# 6_-_Position2Go_Debugger.net
KiCad netlist of a schematic drawn in Altium Designer
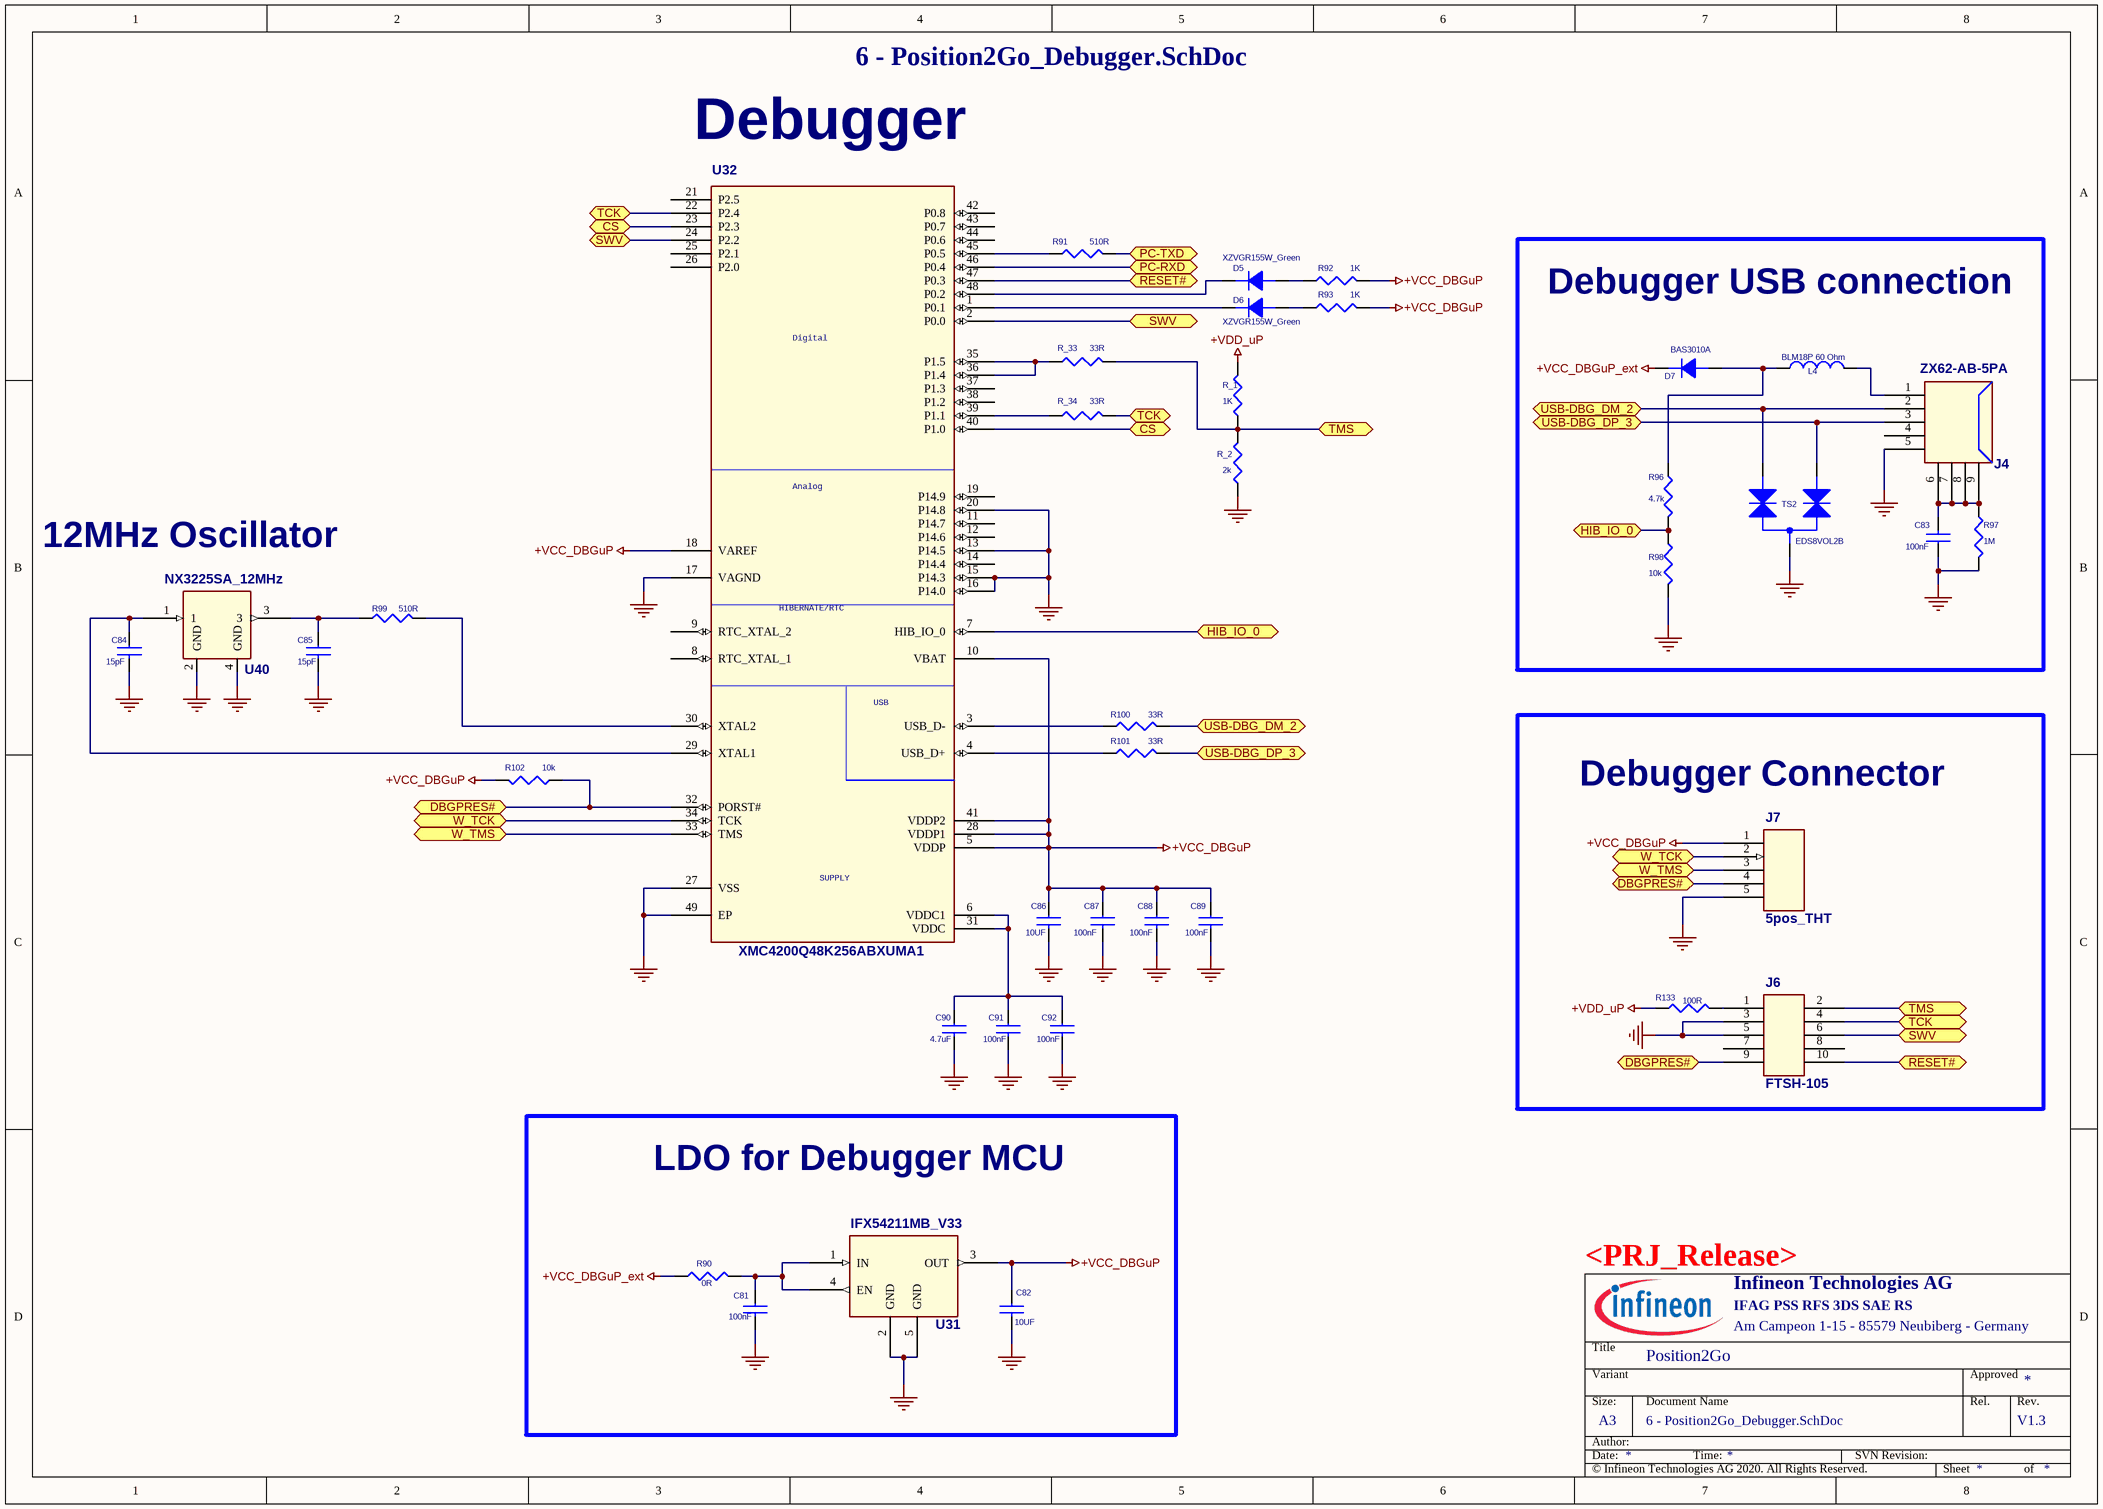
[diagram p0: 6 - Position2Go_Debugger.SchDoc]

(export (version "E")
  (design (tool "Eeschema 10.0.6"))
  (components
    (comp (ref "C81")
      (value "100nF")
      (footprint "0402_durac")
      (description "100nF  ±5%  16V  X7R")
      (fields (field (name "TOLERANCE") "5%") (field (name "VOLTAGE") "16V"))
      (libsource (lib "*") (part "100nF"))
    )
    (comp (ref "C82")
      (value "10UF")
      (footprint "0402_durac")
      (fields (field (name "TOLERANCE") "20%") (field (name "VOLTAGE") "10V"))
      (libsource (lib "*") (part "10UF"))
    )
    (comp (ref "C83")
      (value "100nF")
      (footprint "0402_durac")
      (description "100nF  ±5%  16V  X7R")
      (libsource (lib "*") (part "CAP NP"))
    )
    (comp (ref "C84")
      (value "15pF")
      (footprint "0402_durac")
      (fields (field (name "TOLERANCE") "+-0.1pF") (field (name "VOLTAGE") "50V"))
      (libsource (lib "*") (part "15pF"))
    )
    (comp (ref "C85")
      (value "15pF")
      (footprint "0402_durac")
      (fields (field (name "TOLERANCE") "+-0.1pF") (field (name "VOLTAGE") "50V"))
      (libsource (lib "*") (part "15pF"))
    )
    (comp (ref "C86")
      (value "10UF")
      (footprint "0402_durac")
      (fields (field (name "TOLERANCE") "20%") (field (name "VOLTAGE") "10V"))
      (libsource (lib "*") (part "10UF"))
    )
    (comp (ref "C87")
      (value "100nF")
      (footprint "0402_durac")
      (description "100nF  ±5%  16V  X7R")
      (fields (field (name "TOLERANCE") "5%") (field (name "VOLTAGE") "16V"))
      (libsource (lib "*") (part "100nF"))
    )
    (comp (ref "C88")
      (value "100nF")
      (footprint "0402_durac")
      (description "100nF  ±5%  16V  X7R")
      (fields (field (name "TOLERANCE") "5%") (field (name "VOLTAGE") "16V"))
      (libsource (lib "*") (part "100nF"))
    )
    (comp (ref "C89")
      (value "100nF")
      (footprint "0402_durac")
      (description "100nF  ±5%  16V  X7R")
      (fields (field (name "TOLERANCE") "5%") (field (name "VOLTAGE") "16V"))
      (libsource (lib "*") (part "100nF"))
    )
    (comp (ref "C90")
      (value "4.7uF")
      (footprint "0402_durac")
      (fields (field (name "VOLTAGE") "10V") (field (name "TOLERANCE") "10%"))
      (libsource (lib "*") (part "4.7UF"))
    )
    (comp (ref "C91")
      (value "100nF")
      (footprint "0402_durac")
      (description "100nF  ±5%  16V  X7R")
      (fields (field (name "TOLERANCE") "5%") (field (name "VOLTAGE") "16V"))
      (libsource (lib "*") (part "100nF"))
    )
    (comp (ref "C92")
      (value "100nF")
      (footprint "0402_durac")
      (description "100nF  ±5%  16V  X7R")
      (fields (field (name "TOLERANCE") "5%") (field (name "VOLTAGE") "16V"))
      (libsource (lib "*") (part "100nF"))
    )
    (comp (ref "D5")
      (value "XZVGR155W_Green")
      (footprint "LED_0201")
      (libsource (lib "*") (part "LED_0201_GREEN"))
    )
    (comp (ref "D6")
      (value "XZVGR155W_Green")
      (footprint "LED_0201")
      (libsource (lib "*") (part "LED_0201_GREEN"))
    )
    (comp (ref "D7") (value "BAS3010A") (footprint "sod323") (libsource (lib "*") (part "BAS3010A")))
    (comp (ref "J4")
      (value "ZX62-AB-5PA")
      (footprint "micro_AB_ZX62")
      (libsource (lib "*") (part "CON_MICRO_AB"))
    )
    (comp (ref "J6")
      (value "FTSH-105")
      (footprint "CON_10_pin_uP_FTSH")
      (libsource (lib "*") (part "CON_10_pin_uP_FTSH"))
    )
    (comp (ref "J7")
      (value "5pos_THT")
      (footprint "con_5pin_254p")
      (libsource (lib "*") (part "5pos_TH_passo2_54"))
    )
    (comp (ref "L4")
      (value "BLM18P 60 Ohm")
      (footprint "L_0603")
      (libsource (lib "*") (part "blm18 p 60 ohm"))
    )
    (comp (ref "R90")
      (value "0R")
      (footprint "0402_durac")
      (description "04 0402")
      (fields (field (name "POWER") "0.063W") (field (name "TOLERANCE") "1%"))
      (libsource (lib "*") (part "0_Dup1"))
    )
    (comp (ref "R91")
      (value "510R")
      (footprint "0402_durac")
      (fields (field (name "POWER") "0.063W") (field (name "TOLERANCE") "1%"))
      (libsource (lib "*") (part "510"))
    )
    (comp (ref "R92")
      (value "1K")
      (footprint "R_0201")
      (fields (field (name "POWER") "0.063W") (field (name "TOLERANCE") "1%"))
      (libsource (lib "*") (part "1K"))
    )
    (comp (ref "R93")
      (value "1K")
      (footprint "R_0201")
      (fields (field (name "POWER") "0.063W") (field (name "TOLERANCE") "1%"))
      (libsource (lib "*") (part "1K"))
    )
    (comp (ref "R96")
      (value "4.7k")
      (footprint "0402_durac")
      (fields (field (name "TOLERANCE") "1%") (field (name "POWER") "0.063W"))
      (libsource (lib "*") (part "4.7K"))
    )
    (comp (ref "R97") (value "1M") (footprint "0402_durac") (libsource (lib "*") (part "RESISTOR")))
    (comp (ref "R98")
      (value "10k")
      (footprint "0402_durac")
      (fields (field (name "TOLERANCE") "1%") (field (name "POWER") "0.063W"))
      (libsource (lib "*") (part "10K"))
    )
    (comp (ref "R99")
      (value "510R")
      (footprint "0402_durac")
      (fields (field (name "POWER") "0.063W") (field (name "TOLERANCE") "1%"))
      (libsource (lib "*") (part "510"))
    )
    (comp (ref "R100")
      (value "33R")
      (footprint "0402_durac")
      (fields (field (name "POWER") "0.063W") (field (name "TOLERANCE") "1%"))
      (libsource (lib "*") (part "33"))
    )
    (comp (ref "R101")
      (value "33R")
      (footprint "0402_durac")
      (fields (field (name "POWER") "0.063W") (field (name "TOLERANCE") "1%"))
      (libsource (lib "*") (part "33"))
    )
    (comp (ref "R102")
      (value "10k")
      (footprint "0402_durac")
      (fields (field (name "TOLERANCE") "1%") (field (name "POWER") "0.063W"))
      (libsource (lib "*") (part "10K"))
    )
    (comp (ref "R133") (value "100R") (footprint "0402_durac") (libsource (lib "*") (part "RESISTOR")))
    (comp (ref "R_1")
      (value "1K")
      (footprint "R_0201")
      (fields (field (name "POWER") "0.063W") (field (name "TOLERANCE") "1%"))
      (libsource (lib "*") (part "1K"))
    )
    (comp (ref "R_2")
      (value "2k")
      (footprint "R_0201")
      (fields (field (name "POWER") "0.063W") (field (name "TOLERANCE") "1%"))
      (libsource (lib "*") (part "1K"))
    )
    (comp (ref "R_33")
      (value "33R")
      (footprint "R_0201")
      (fields (field (name "POWER") "0.063W") (field (name "TOLERANCE") "1%"))
      (libsource (lib "*") (part "1K"))
    )
    (comp (ref "R_34")
      (value "33R")
      (footprint "R_0201")
      (fields (field (name "POWER") "0.063W") (field (name "TOLERANCE") "1%"))
      (libsource (lib "*") (part "1K"))
    )
    (comp (ref "TS2") (value "EDS8VOL2B") (footprint "ESD8VOL2B") (libsource (lib "*") (part "ESD8VOL2B")))
    (comp (ref "U31")
      (value "IFX54211MB_V33")
      (footprint "inf-pg-sct595v")
      (libsource (lib "*") (part "IFX54211MB_V33"))
    )
    (comp (ref "U32")
      (value "XMC4200Q48K256ABXUMA1")
      (footprint "inf-pg-vqfn-48-_-5200x5200tp_n")
      (libsource (lib "*") (part "XMC4200_VQFN48"))
    )
    (comp (ref "U40")
      (value "NX3225SA_12MHz")
      (footprint "NX3225SA")
      (description "NX3225SA-12.000M-STD-CRS-2")
      (libsource (lib "*") (part "NX3225SA_12MHZ"))
    )
  )
  (nets
    (net (code "1") (name "+VCC_DBGuP") (class "Default")
      (node (ref "C82") (pin "1") (pinfunction "1_1") (pintype "passive"))
      (node (ref "C86") (pin "1") (pinfunction "1_1") (pintype "passive"))
      (node (ref "C87") (pin "1") (pinfunction "1_1") (pintype "passive"))
      (node (ref "C88") (pin "1") (pinfunction "1_1") (pintype "passive"))
      (node (ref "C89") (pin "1") (pinfunction "1_1") (pintype "passive"))
      (node (ref "J7") (pin "1") (pinfunction "1_1") (pintype "passive"))
      (node (ref "R102") (pin "2") (pinfunction "2_2") (pintype "passive"))
      (node (ref "R92") (pin "2") (pinfunction "2_2") (pintype "passive"))
      (node (ref "R93") (pin "2") (pinfunction "2_2") (pintype "passive"))
      (node (ref "U31") (pin "3") (pinfunction "OUT_3") (pintype "output"))
      (node (ref "U32") (pin "10") (pinfunction "VBAT_10") (pintype "power_in"))
      (node (ref "U32") (pin "18") (pinfunction "VAREF_18") (pintype "power_in"))
      (node (ref "U32") (pin "28") (pinfunction "VDDP1_28") (pintype "power_in"))
      (node (ref "U32") (pin "41") (pinfunction "VDDP2_41") (pintype "power_in"))
      (node (ref "U32") (pin "5") (pinfunction "VDDP_5") (pintype "power_in"))
    )
    (net (code "2") (name "+VCC_DBGuP_ext") (class "Default")
      (node (ref "D7") (pin "1") (pinfunction "K_1") (pintype "passive"))
      (node (ref "R90") (pin "1") (pinfunction "1_1") (pintype "passive"))
    )
    (net (code "3") (name "+VDD_uP") (class "Default")
      (node (ref "R133") (pin "2") (pinfunction "2_2") (pintype "passive"))
      (node (ref "R_1") (pin "2") (pinfunction "2_2") (pintype "passive"))
    )
    (net (code "4") (name "/CS") (class "Default")
      (node (ref "U32") (pin "23") (pinfunction "P2.3_23") (pintype "passive"))
      (node (ref "U32") (pin "40") (pinfunction "P1.0_40") (pintype "bidirectional"))
    )
    (net (code "5") (name "/DBGPRES#") (class "Default")
      (node (ref "J6") (pin "9") (pinfunction "9_9") (pintype "passive"))
      (node (ref "J7") (pin "4") (pinfunction "4_4") (pintype "passive"))
      (node (ref "R102") (pin "1") (pinfunction "1_1") (pintype "passive"))
      (node (ref "U32") (pin "32") (pinfunction "PORST#_32") (pintype "bidirectional"))
    )
    (net (code "6") (name "/HIB_IO_0") (class "Default")
      (node (ref "R96") (pin "2") (pinfunction "2_2") (pintype "passive"))
      (node (ref "R98") (pin "1") (pinfunction "1_1") (pintype "passive"))
      (node (ref "U32") (pin "7") (pinfunction "HIB_IO_0_7") (pintype "bidirectional"))
    )
    (net (code "7") (name "/PC-RXD") (class "Default")
      (node (ref "U32") (pin "46") (pinfunction "P0.4_46") (pintype "bidirectional"))
    )
    (net (code "8") (name "/PC-TXD") (class "Default")
      (node (ref "R91") (pin "2") (pinfunction "2_2") (pintype "passive"))
    )
    (net (code "9") (name "/RESET#") (class "Default")
      (node (ref "J6") (pin "10") (pinfunction "10_10") (pintype "passive"))
      (node (ref "U32") (pin "47") (pinfunction "P0.3_47") (pintype "bidirectional"))
    )
    (net (code "10") (name "/SWV") (class "Default")
      (node (ref "J6") (pin "6") (pinfunction "6_6") (pintype "passive"))
      (node (ref "U32") (pin "2") (pinfunction "P0.0_2") (pintype "bidirectional"))
      (node (ref "U32") (pin "24") (pinfunction "P2.2_24") (pintype "passive"))
    )
    (net (code "11") (name "/TCK") (class "Default")
      (node (ref "J6") (pin "4") (pinfunction "4_4") (pintype "passive"))
      (node (ref "R_34") (pin "2") (pinfunction "2_2") (pintype "passive"))
      (node (ref "U32") (pin "22") (pinfunction "P2.4_22") (pintype "passive"))
    )
    (net (code "12") (name "/TMS") (class "Default")
      (node (ref "J6") (pin "2") (pinfunction "2_2") (pintype "passive"))
      (node (ref "R_1") (pin "1") (pinfunction "1_1") (pintype "passive"))
      (node (ref "R_2") (pin "2") (pinfunction "2_2") (pintype "passive"))
      (node (ref "R_33") (pin "2") (pinfunction "2_2") (pintype "passive"))
    )
    (net (code "13") (name "/USB-DBG_DM_2") (class "Default")
      (node (ref "J4") (pin "2") (pinfunction "2_2") (pintype "passive"))
      (node (ref "R100") (pin "2") (pinfunction "2_2") (pintype "passive"))
      (node (ref "TS2") (pin "1") (pinfunction "1_1") (pintype "passive"))
    )
    (net (code "14") (name "/USB-DBG_DP_3") (class "Default")
      (node (ref "J4") (pin "3") (pinfunction "3_3") (pintype "passive"))
      (node (ref "R101") (pin "2") (pinfunction "2_2") (pintype "passive"))
      (node (ref "TS2") (pin "2") (pinfunction "2_2") (pintype "passive"))
    )
    (net (code "15") (name "/W_TCK") (class "Default")
      (node (ref "J7") (pin "2") (pinfunction "2_2") (pintype "input"))
      (node (ref "U32") (pin "34") (pinfunction "TCK_34") (pintype "bidirectional"))
    )
    (net (code "16") (name "/W_TMS") (class "Default")
      (node (ref "J7") (pin "3") (pinfunction "3_3") (pintype "passive"))
      (node (ref "U32") (pin "33") (pinfunction "TMS_33") (pintype "bidirectional"))
    )
    (net (code "17") (name "GND_POWER") (class "Default")
      (node (ref "C81") (pin "2") (pinfunction "2_2") (pintype "passive"))
      (node (ref "C82") (pin "2") (pinfunction "2_2") (pintype "passive"))
      (node (ref "C83") (pin "1") (pinfunction "1_1") (pintype "passive"))
      (node (ref "C84") (pin "2") (pinfunction "2_2") (pintype "passive"))
      (node (ref "C85") (pin "2") (pinfunction "2_2") (pintype "passive"))
      (node (ref "C86") (pin "2") (pinfunction "2_2") (pintype "passive"))
      (node (ref "C87") (pin "2") (pinfunction "2_2") (pintype "passive"))
      (node (ref "C88") (pin "2") (pinfunction "2_2") (pintype "passive"))
      (node (ref "C89") (pin "2") (pinfunction "2_2") (pintype "passive"))
      (node (ref "C90") (pin "2") (pinfunction "2_2") (pintype "passive"))
      (node (ref "C91") (pin "2") (pinfunction "2_2") (pintype "passive"))
      (node (ref "C92") (pin "2") (pinfunction "2_2") (pintype "passive"))
      (node (ref "J4") (pin "5") (pinfunction "5_5") (pintype "passive"))
      (node (ref "J6") (pin "3") (pinfunction "3_3") (pintype "passive"))
      (node (ref "J6") (pin "5") (pinfunction "5_5") (pintype "passive"))
      (node (ref "J7") (pin "5") (pinfunction "5_5") (pintype "passive"))
      (node (ref "R97") (pin "2") (pinfunction "2_2") (pintype "passive"))
      (node (ref "R98") (pin "2") (pinfunction "2_2") (pintype "passive"))
      (node (ref "R_2") (pin "1") (pinfunction "1_1") (pintype "passive"))
      (node (ref "TS2") (pin "3") (pinfunction "3_3") (pintype "passive"))
      (node (ref "U31") (pin "2") (pinfunction "GND_2") (pintype "power_in"))
      (node (ref "U31") (pin "5") (pinfunction "GND_5") (pintype "power_in"))
      (node (ref "U32") (pin "13") (pinfunction "P14.5_13") (pintype "bidirectional"))
      (node (ref "U32") (pin "15") (pinfunction "P14.3_15") (pintype "bidirectional"))
      (node (ref "U32") (pin "16") (pinfunction "P14.0_16") (pintype "bidirectional"))
      (node (ref "U32") (pin "17") (pinfunction "VAGND_17") (pintype "power_in"))
      (node (ref "U32") (pin "20") (pinfunction "P14.8_20") (pintype "bidirectional"))
      (node (ref "U32") (pin "27") (pinfunction "VSS_27") (pintype "power_in"))
      (node (ref "U32") (pin "49") (pinfunction "EP_49") (pintype "power_in"))
      (node (ref "U40") (pin "2") (pinfunction "GND_2") (pintype "power_in"))
      (node (ref "U40") (pin "4") (pinfunction "GND_4") (pintype "power_in"))
    )
    (net (code "18") (name "Net-(C85-Pad1)") (class "Default")
      (node (ref "C85") (pin "1") (pinfunction "1_1") (pintype "passive"))
      (node (ref "R99") (pin "1") (pinfunction "1_1") (pintype "passive"))
      (node (ref "U40") (pin "3") (pinfunction "3_3") (pintype "output"))
    )
    (net (code "19") (name "Net-(D5-A)") (class "Default")
      (node (ref "D5") (pin "2") (pinfunction "A_2") (pintype "passive"))
      (node (ref "R92") (pin "1") (pinfunction "1_1") (pintype "passive"))
    )
    (net (code "20") (name "Net-(D5-K)") (class "Default")
      (node (ref "D5") (pin "1") (pinfunction "K_1") (pintype "passive"))
      (node (ref "U32") (pin "48") (pinfunction "P0.2_48") (pintype "bidirectional"))
    )
    (net (code "21") (name "Net-(D6-A)") (class "Default")
      (node (ref "D6") (pin "2") (pinfunction "A_2") (pintype "passive"))
      (node (ref "R93") (pin "1") (pinfunction "1_1") (pintype "passive"))
    )
    (net (code "22") (name "Net-(D6-K)") (class "Default")
      (node (ref "D6") (pin "1") (pinfunction "K_1") (pintype "passive"))
      (node (ref "U32") (pin "1") (pinfunction "P0.1_1") (pintype "bidirectional"))
    )
    (net (code "23") (name "Net-(D7-A)") (class "Default")
      (node (ref "D7") (pin "2") (pinfunction "A_2") (pintype "passive"))
      (node (ref "L4") (pin "2") (pinfunction "2_2") (pintype "passive"))
      (node (ref "R96") (pin "1") (pinfunction "1_1") (pintype "passive"))
    )
    (net (code "24") (name "Net-(J4-GNd)") (class "Default")
      (node (ref "C83") (pin "2") (pinfunction "2_2") (pintype "passive"))
      (node (ref "J4") (pin "6") (pinfunction "GND_6") (pintype "power_in"))
      (node (ref "J4") (pin "7") (pinfunction "GND_7") (pintype "power_in"))
      (node (ref "J4") (pin "8") (pinfunction "GND_8") (pintype "power_in"))
      (node (ref "J4") (pin "9") (pinfunction "GNd_9") (pintype "power_in"))
      (node (ref "R97") (pin "1") (pinfunction "1_1") (pintype "passive"))
    )
    (net (code "25") (name "Net-(J4-Pad1)") (class "Default")
      (node (ref "J4") (pin "1") (pinfunction "1_1") (pintype "passive"))
      (node (ref "L4") (pin "1") (pinfunction "1_1") (pintype "passive"))
    )
    (net (code "26") (name "Net-(J6-Pad1)") (class "Default")
      (node (ref "J6") (pin "1") (pinfunction "1_1") (pintype "passive"))
      (node (ref "R133") (pin "1") (pinfunction "1_1") (pintype "passive"))
    )
    (net (code "27") (name "Net-(U31-EN)") (class "Default")
      (node (ref "C81") (pin "1") (pinfunction "1_1") (pintype "passive"))
      (node (ref "R90") (pin "2") (pinfunction "2_2") (pintype "passive"))
      (node (ref "U31") (pin "1") (pinfunction "IN_1") (pintype "input"))
      (node (ref "U31") (pin "4") (pinfunction "EN_4") (pintype "output"))
    )
    (net (code "28") (name "Net-(U32-P0.5)") (class "Default")
      (node (ref "R91") (pin "1") (pinfunction "1_1") (pintype "passive"))
      (node (ref "U32") (pin "45") (pinfunction "P0.5_45") (pintype "bidirectional"))
    )
    (net (code "29") (name "Net-(U32-P1.1)") (class "Default")
      (node (ref "R_34") (pin "1") (pinfunction "1_1") (pintype "passive"))
      (node (ref "U32") (pin "39") (pinfunction "P1.1_39") (pintype "bidirectional"))
    )
    (net (code "30") (name "Net-(U32-P1.4)") (class "Default")
      (node (ref "R_33") (pin "1") (pinfunction "1_1") (pintype "passive"))
      (node (ref "U32") (pin "35") (pinfunction "P1.5_35") (pintype "bidirectional"))
      (node (ref "U32") (pin "36") (pinfunction "P1.4_36") (pintype "bidirectional"))
    )
    (net (code "31") (name "Net-(U32-USB_D+)") (class "Default")
      (node (ref "R101") (pin "1") (pinfunction "1_1") (pintype "passive"))
      (node (ref "U32") (pin "4") (pinfunction "USB_D+_4") (pintype "bidirectional"))
    )
    (net (code "32") (name "Net-(U32-USB_D-)") (class "Default")
      (node (ref "R100") (pin "1") (pinfunction "1_1") (pintype "passive"))
      (node (ref "U32") (pin "3") (pinfunction "USB_D-_3") (pintype "bidirectional"))
    )
    (net (code "33") (name "Net-(U32-VDDC)") (class "Default")
      (node (ref "C90") (pin "1") (pinfunction "1_1") (pintype "passive"))
      (node (ref "C91") (pin "1") (pinfunction "1_1") (pintype "passive"))
      (node (ref "C92") (pin "1") (pinfunction "1_1") (pintype "passive"))
      (node (ref "U32") (pin "31") (pinfunction "VDDC_31") (pintype "power_in"))
      (node (ref "U32") (pin "6") (pinfunction "VDDC1_6") (pintype "power_in"))
    )
    (net (code "34") (name "Net-(U32-XTAL1)") (class "Default")
      (node (ref "C84") (pin "1") (pinfunction "1_1") (pintype "passive"))
      (node (ref "U32") (pin "29") (pinfunction "XTAL1_29") (pintype "bidirectional"))
      (node (ref "U40") (pin "1") (pinfunction "1_1") (pintype "input"))
    )
    (net (code "35") (name "Net-(U32-XTAL2)") (class "Default")
      (node (ref "R99") (pin "2") (pinfunction "2_2") (pintype "passive"))
      (node (ref "U32") (pin "30") (pinfunction "XTAL2_30") (pintype "bidirectional"))
    )
    (net (code "36") (name "unconnected-(J4-Pad4)") (class "Default")
      (node (ref "J4") (pin "4") (pinfunction "4_4") (pintype "passive"))
    )
    (net (code "37") (name "unconnected-(J6-Pad7)") (class "Default")
      (node (ref "J6") (pin "7") (pinfunction "7_7") (pintype "passive"))
    )
    (net (code "38") (name "unconnected-(J6-Pad8)") (class "Default")
      (node (ref "J6") (pin "8") (pinfunction "8_8") (pintype "passive"))
    )
    (net (code "39") (name "unconnected-(U32-P0.6-Pad44)") (class "Default")
      (node (ref "U32") (pin "44") (pinfunction "P0.6_44") (pintype "bidirectional"))
    )
    (net (code "40") (name "unconnected-(U32-P0.7-Pad43)") (class "Default")
      (node (ref "U32") (pin "43") (pinfunction "P0.7_43") (pintype "bidirectional"))
    )
    (net (code "41") (name "unconnected-(U32-P0.8-Pad42)") (class "Default")
      (node (ref "U32") (pin "42") (pinfunction "P0.8_42") (pintype "bidirectional"))
    )
    (net (code "42") (name "unconnected-(U32-P1.2-Pad38)") (class "Default")
      (node (ref "U32") (pin "38") (pinfunction "P1.2_38") (pintype "bidirectional"))
    )
    (net (code "43") (name "unconnected-(U32-P1.3-Pad37)") (class "Default")
      (node (ref "U32") (pin "37") (pinfunction "P1.3_37") (pintype "bidirectional"))
    )
    (net (code "44") (name "unconnected-(U32-P2.0-Pad26)") (class "Default")
      (node (ref "U32") (pin "26") (pinfunction "P2.0_26") (pintype "passive"))
    )
    (net (code "45") (name "unconnected-(U32-P2.1-Pad25)") (class "Default")
      (node (ref "U32") (pin "25") (pinfunction "P2.1_25") (pintype "passive"))
    )
    (net (code "46") (name "unconnected-(U32-P2.5-Pad21)") (class "Default")
      (node (ref "U32") (pin "21") (pinfunction "P2.5_21") (pintype "passive"))
    )
    (net (code "47") (name "unconnected-(U32-P14.4-Pad14)") (class "Default")
      (node (ref "U32") (pin "14") (pinfunction "P14.4_14") (pintype "bidirectional"))
    )
    (net (code "48") (name "unconnected-(U32-P14.6-Pad12)") (class "Default")
      (node (ref "U32") (pin "12") (pinfunction "P14.6_12") (pintype "bidirectional"))
    )
    (net (code "49") (name "unconnected-(U32-P14.7-Pad11)") (class "Default")
      (node (ref "U32") (pin "11") (pinfunction "P14.7_11") (pintype "bidirectional"))
    )
    (net (code "50") (name "unconnected-(U32-P14.9-Pad19)") (class "Default")
      (node (ref "U32") (pin "19") (pinfunction "P14.9_19") (pintype "bidirectional"))
    )
    (net (code "51") (name "unconnected-(U32-RTC_XTAL_1-Pad8)") (class "Default")
      (node (ref "U32") (pin "8") (pinfunction "RTC_XTAL_1_8") (pintype "bidirectional"))
    )
    (net (code "52") (name "unconnected-(U32-RTC_XTAL_2-Pad9)") (class "Default")
      (node (ref "U32") (pin "9") (pinfunction "RTC_XTAL_2_9") (pintype "bidirectional"))
    )
  )
)
